# KEY_GPIO_NANDF_ENET.net
KiCad netlist of a schematic drawn in Altium Designer
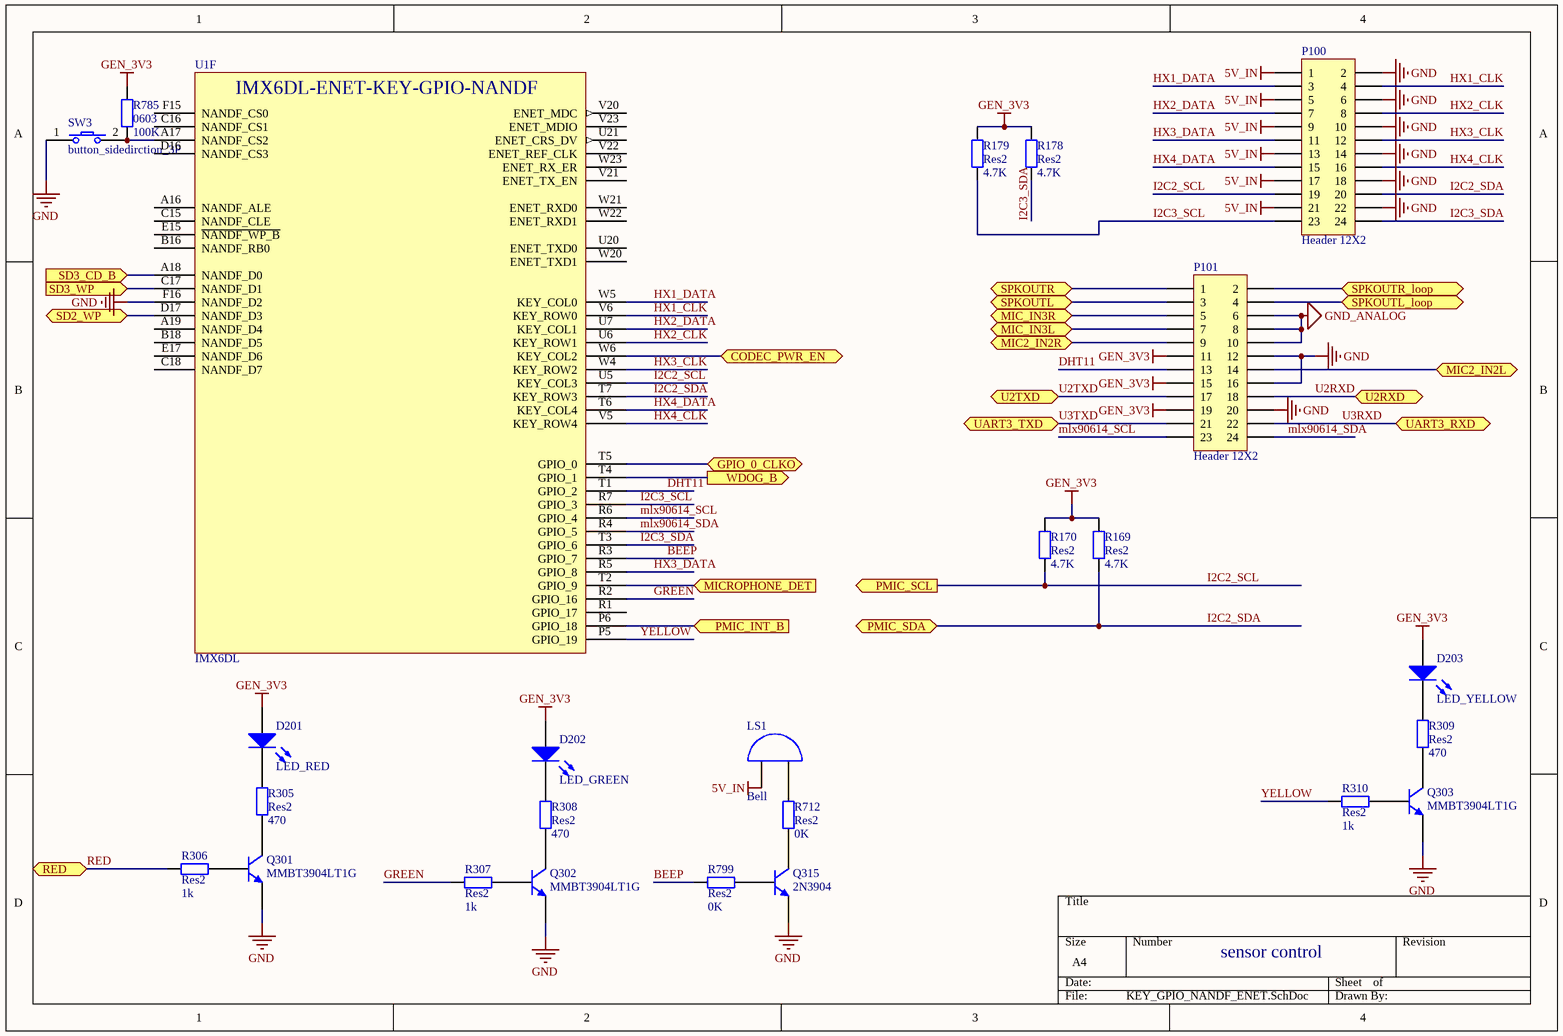
[diagram p0: KEY_GPIO_NANDF_ENET.SchDoc]

(export (version "E")
  (design (tool "Eeschema 10.0.6"))
  (components
    (comp (ref "D201")
      (value "LED_RED")
      (footprint "LED_0603")
      (description "Typical INFRARED GaAs LED")
      (fields (field (name "PUBLISHER") "Altium Limited"))
      (libsource (lib "Miscellaneous Devices") (part "LED0"))
    )
    (comp (ref "D202")
      (value "LED_GREEN")
      (footprint "LED_0603")
      (description "Typical INFRARED GaAs LED")
      (fields (field (name "PUBLISHER") "Altium Limited"))
      (libsource (lib "Miscellaneous Devices") (part "LED0"))
    )
    (comp (ref "D203")
      (value "LED_YELLOW")
      (footprint "LED_0603")
      (description "Typical INFRARED GaAs LED")
      (fields (field (name "PUBLISHER") "Altium Limited"))
      (libsource (lib "Miscellaneous Devices") (part "LED0"))
    )
    (comp (ref "LS1")
      (value "Bell")
      (footprint "PIN2")
      (description "Electrical Bell")
      (fields (field (name "PUBLISHER") "Altium Limited"))
      (libsource (lib "Miscellaneous Devices") (part "Bell"))
    )
    (comp (ref "P100")
      (value "Header 12X2")
      (footprint "Double Row _DIP43025- 2P-24P")
      (description "Header, 12-Pin, Dual row")
      (fields (field (name "PUBLISHER") "Altium Limited"))
      (libsource (lib "Miscellaneous Connectors") (part "Header 12X2"))
    )
    (comp (ref "P101")
      (value "Header 12X2")
      (footprint "Double Row _DIP43025- 2P-24P")
      (description "Header, 12-Pin, Dual row")
      (fields (field (name "PUBLISHER") "Altium Limited"))
      (libsource (lib "Miscellaneous Connectors") (part "Header 12X2"))
    )
    (comp (ref "Q301")
      (value "MMBT3904LT1G")
      (footprint "MMBT3904LT1G-SOT23")
      (libsource (lib "IMX6DL") (part "MMBT3904LT1G"))
    )
    (comp (ref "Q302")
      (value "MMBT3904LT1G")
      (footprint "MMBT3904LT1G-SOT23")
      (libsource (lib "IMX6DL") (part "MMBT3904LT1G"))
    )
    (comp (ref "Q303")
      (value "MMBT3904LT1G")
      (footprint "MMBT3904LT1G-SOT23")
      (libsource (lib "IMX6DL") (part "MMBT3904LT1G"))
    )
    (comp (ref "Q315")
      (value "2N3904")
      (footprint "BCY-W3/E4")
      (description "NPN General Purpose Amplifier")
      (fields (field (name "PUBLISHER") "Altium Limited"))
      (libsource (lib "Miscellaneous Devices") (part "2N3904"))
    )
    (comp (ref "R169")
      (value "Res2")
      (footprint "0402")
      (description "Resistor")
      (fields (field (name "ALTIUM_VALUE") "4.7K") (field (name "PUBLISHER") "Altium Limited"))
      (libsource (lib "") (part "Res2_2"))
    )
    (comp (ref "R170")
      (value "Res2")
      (footprint "0402")
      (description "Resistor")
      (fields (field (name "ALTIUM_VALUE") "4.7K") (field (name "PUBLISHER") "Altium Limited"))
      (libsource (lib "") (part "Res2_2"))
    )
    (comp (ref "R178")
      (value "Res2")
      (footprint "0402")
      (description "Resistor")
      (fields (field (name "ALTIUM_VALUE") "4.7K") (field (name "PUBLISHER") "Altium Limited"))
      (libsource (lib "") (part "Res2_2"))
    )
    (comp (ref "R179")
      (value "Res2")
      (footprint "0402")
      (description "Resistor")
      (fields (field (name "ALTIUM_VALUE") "4.7K") (field (name "PUBLISHER") "Altium Limited"))
      (libsource (lib "") (part "Res2_2"))
    )
    (comp (ref "R305")
      (value "Res2")
      (footprint "0603")
      (description "Resistor")
      (fields (field (name "ALTIUM_VALUE") "470") (field (name "PUBLISHER") "Altium Limited"))
      (libsource (lib "") (part "Res2_2"))
    )
    (comp (ref "R306")
      (value "Res2")
      (footprint "0603")
      (description "Resistor")
      (fields (field (name "ALTIUM_VALUE") "1k") (field (name "PUBLISHER") "Altium Limited"))
      (libsource (lib "Miscellaneous Devices") (part "Res2"))
    )
    (comp (ref "R307")
      (value "Res2")
      (footprint "0603")
      (description "Resistor")
      (fields (field (name "ALTIUM_VALUE") "1k") (field (name "PUBLISHER") "Altium Limited"))
      (libsource (lib "Miscellaneous Devices") (part "Res2"))
    )
    (comp (ref "R308")
      (value "Res2")
      (footprint "0603")
      (description "Resistor")
      (fields (field (name "ALTIUM_VALUE") "470") (field (name "PUBLISHER") "Altium Limited"))
      (libsource (lib "") (part "Res2_2"))
    )
    (comp (ref "R309")
      (value "Res2")
      (footprint "0603")
      (description "Resistor")
      (fields (field (name "ALTIUM_VALUE") "470") (field (name "PUBLISHER") "Altium Limited"))
      (libsource (lib "") (part "Res2_2"))
    )
    (comp (ref "R310")
      (value "Res2")
      (footprint "0603")
      (description "Resistor")
      (fields (field (name "ALTIUM_VALUE") "1k") (field (name "PUBLISHER") "Altium Limited"))
      (libsource (lib "Miscellaneous Devices") (part "Res2"))
    )
    (comp (ref "R712")
      (value "Res2")
      (footprint "0603")
      (description "Resistor")
      (fields (field (name "ALTIUM_VALUE") "0K") (field (name "PUBLISHER") "Altium Limited"))
      (libsource (lib "") (part "Res2_1"))
    )
    (comp (ref "R785")
      (value "0603")
      (footprint "0603")
      (description "Resistor")
      (fields (field (name "ALTIUM_VALUE") "100K") (field (name "PUBLISHER") "Altium Limited"))
      (libsource (lib "") (part "Res2_2"))
    )
    (comp (ref "R799")
      (value "Res2")
      (footprint "0603")
      (description "Resistor")
      (fields (field (name "ALTIUM_VALUE") "0K") (field (name "PUBLISHER") "Altium Limited"))
      (libsource (lib "Miscellaneous Devices") (part "Res2"))
    )
    (comp (ref "SW3")
      (value "button_sidedirction_3P")
      (footprint "button_sidedirction_3P 4.5X4.5")
      (libsource (lib "IMX6DL") (part "button_sidedirction_3P"))
    )
    (comp (ref "U1")
      (value "IMX6DL")
      (footprint "IMX6DL-BGA624x25")
      (libsource (lib "IMX6DL") (part "IMX6DL"))
    )
  )
  (nets
    (net (code "1") (name "/BEEP") (class "Default")
      (node (ref "R799") (pin "2") (pinfunction "2_2") (pintype "passive"))
      (node (ref "U1") (pin "R3") (pinfunction "GPIO_7_R3") (pintype "passive"))
    )
    (net (code "2") (name "/CODEC_PWR_EN") (class "Default")
      (node (ref "U1") (pin "W6") (pinfunction "KEY_COL2_W6") (pintype "passive"))
    )
    (net (code "3") (name "/DHT11") (class "Default")
      (node (ref "P101") (pin "13") (pinfunction "13_13") (pintype "passive"))
      (node (ref "U1") (pin "T1") (pinfunction "GPIO_2_T1") (pintype "passive"))
    )
    (net (code "4") (name "/GPIO_0_CLKO") (class "Default")
      (node (ref "U1") (pin "T5") (pinfunction "GPIO_0_T5") (pintype "passive"))
    )
    (net (code "5") (name "/GREEN") (class "Default")
      (node (ref "R307") (pin "2") (pinfunction "2_2") (pintype "passive"))
      (node (ref "U1") (pin "R2") (pinfunction "GPIO_16_R2") (pintype "passive"))
    )
    (net (code "6") (name "/HX1_CLK") (class "Default")
      (node (ref "P100") (pin "4") (pinfunction "4_4") (pintype "passive"))
      (node (ref "U1") (pin "V6") (pinfunction "KEY_ROW0_V6") (pintype "passive"))
    )
    (net (code "7") (name "/HX1_DATA") (class "Default")
      (node (ref "P100") (pin "3") (pinfunction "3_3") (pintype "passive"))
      (node (ref "U1") (pin "W5") (pinfunction "KEY_COL0_W5") (pintype "passive"))
    )
    (net (code "8") (name "/HX2_CLK") (class "Default")
      (node (ref "P100") (pin "8") (pinfunction "8_8") (pintype "passive"))
      (node (ref "U1") (pin "U6") (pinfunction "KEY_ROW1_U6") (pintype "passive"))
    )
    (net (code "9") (name "/HX2_DATA") (class "Default")
      (node (ref "P100") (pin "7") (pinfunction "7_7") (pintype "passive"))
      (node (ref "U1") (pin "U7") (pinfunction "KEY_COL1_U7") (pintype "passive"))
    )
    (net (code "10") (name "/HX3_CLK") (class "Default")
      (node (ref "P100") (pin "12") (pinfunction "12_12") (pintype "passive"))
      (node (ref "U1") (pin "W4") (pinfunction "KEY_ROW2_W4") (pintype "passive"))
    )
    (net (code "11") (name "/HX3_DATA") (class "Default")
      (node (ref "P100") (pin "11") (pinfunction "11_11") (pintype "passive"))
      (node (ref "U1") (pin "R5") (pinfunction "GPIO_8_R5") (pintype "passive"))
    )
    (net (code "12") (name "/HX4_CLK") (class "Default")
      (node (ref "P100") (pin "16") (pinfunction "16_16") (pintype "passive"))
      (node (ref "U1") (pin "V5") (pinfunction "KEY_ROW4_V5") (pintype "passive"))
    )
    (net (code "13") (name "/HX4_DATA") (class "Default")
      (node (ref "P100") (pin "15") (pinfunction "15_15") (pintype "passive"))
      (node (ref "U1") (pin "T6") (pinfunction "KEY_COL4_T6") (pintype "passive"))
    )
    (net (code "14") (name "/I2C2_SCL") (class "Default")
      (node (ref "P100") (pin "19") (pinfunction "19_19") (pintype "passive"))
      (node (ref "R170") (pin "1") (pinfunction "1_1") (pintype "passive"))
      (node (ref "U1") (pin "U5") (pinfunction "KEY_COL3_U5") (pintype "passive"))
    )
    (net (code "15") (name "/I2C2_SDA") (class "Default")
      (node (ref "P100") (pin "20") (pinfunction "20_20") (pintype "passive"))
      (node (ref "R169") (pin "1") (pinfunction "1_1") (pintype "passive"))
      (node (ref "U1") (pin "T7") (pinfunction "KEY_ROW3_T7") (pintype "passive"))
    )
    (net (code "16") (name "/I2C3_SCL") (class "Default")
      (node (ref "P100") (pin "23") (pinfunction "23_23") (pintype "passive"))
      (node (ref "R179") (pin "1") (pinfunction "1_1") (pintype "passive"))
      (node (ref "U1") (pin "R7") (pinfunction "GPIO_3_R7") (pintype "passive"))
    )
    (net (code "17") (name "/I2C3_SDA") (class "Default")
      (node (ref "P100") (pin "24") (pinfunction "24_24") (pintype "passive"))
      (node (ref "R178") (pin "1") (pinfunction "1_1") (pintype "passive"))
      (node (ref "U1") (pin "T3") (pinfunction "GPIO_6_T3") (pintype "passive"))
    )
    (net (code "18") (name "/MIC2_IN2L") (class "Default")
      (node (ref "P101") (pin "14") (pinfunction "14_14") (pintype "passive"))
    )
    (net (code "19") (name "/MIC2_IN2R") (class "Default")
      (node (ref "P101") (pin "9") (pinfunction "9_9") (pintype "passive"))
    )
    (net (code "20") (name "/MICROPHONE_DET") (class "Default")
      (node (ref "U1") (pin "T2") (pinfunction "GPIO_9_T2") (pintype "passive"))
    )
    (net (code "21") (name "/MIC_IN3L") (class "Default")
      (node (ref "P101") (pin "7") (pinfunction "7_7") (pintype "passive"))
    )
    (net (code "22") (name "/MIC_IN3R") (class "Default")
      (node (ref "P101") (pin "5") (pinfunction "5_5") (pintype "passive"))
    )
    (net (code "23") (name "/PMIC_INT_B") (class "Default")
      (node (ref "U1") (pin "P6") (pinfunction "GPIO_18_P6") (pintype "passive"))
    )
    (net (code "24") (name "/RED") (class "Default")
      (node (ref "R306") (pin "2") (pinfunction "2_2") (pintype "passive"))
    )
    (net (code "25") (name "/SD2_WP") (class "Default")
      (node (ref "U1") (pin "D17") (pinfunction "NANDF_D3_D17") (pintype "passive"))
    )
    (net (code "26") (name "/SD3_CD_B") (class "Default")
      (node (ref "U1") (pin "A18") (pinfunction "NANDF_D0_A18") (pintype "passive"))
    )
    (net (code "27") (name "/SD3_WP") (class "Default")
      (node (ref "U1") (pin "C17") (pinfunction "NANDF_D1_C17") (pintype "passive"))
    )
    (net (code "28") (name "/SPKOUTL") (class "Default")
      (node (ref "P101") (pin "3") (pinfunction "3_3") (pintype "passive"))
    )
    (net (code "29") (name "/SPKOUTL_loop") (class "Default")
      (node (ref "P101") (pin "4") (pinfunction "4_4") (pintype "passive"))
    )
    (net (code "30") (name "/SPKOUTR") (class "Default")
      (node (ref "P101") (pin "1") (pinfunction "1_1") (pintype "passive"))
    )
    (net (code "31") (name "/SPKOUTR_loop") (class "Default")
      (node (ref "P101") (pin "2") (pinfunction "2_2") (pintype "passive"))
    )
    (net (code "32") (name "/U2RXD") (class "Default")
      (node (ref "P101") (pin "18") (pinfunction "18_18") (pintype "passive"))
    )
    (net (code "33") (name "/U2TXD") (class "Default")
      (node (ref "P101") (pin "17") (pinfunction "17_17") (pintype "passive"))
    )
    (net (code "34") (name "/U3RXD") (class "Default")
      (node (ref "P101") (pin "22") (pinfunction "22_22") (pintype "passive"))
    )
    (net (code "35") (name "/U3TXD") (class "Default")
      (node (ref "P101") (pin "21") (pinfunction "21_21") (pintype "passive"))
    )
    (net (code "36") (name "/WDOG_B") (class "Default")
      (node (ref "U1") (pin "T4") (pinfunction "GPIO_1_T4") (pintype "passive"))
    )
    (net (code "37") (name "/YELLOW") (class "Default")
      (node (ref "R310") (pin "2") (pinfunction "2_2") (pintype "passive"))
      (node (ref "U1") (pin "P5") (pinfunction "GPIO_19_P5") (pintype "passive"))
    )
    (net (code "38") (name "/mlx90614_SCL") (class "Default")
      (node (ref "P101") (pin "23") (pinfunction "23_23") (pintype "passive"))
      (node (ref "U1") (pin "R6") (pinfunction "GPIO_4_R6") (pintype "passive"))
    )
    (net (code "39") (name "/mlx90614_SDA") (class "Default")
      (node (ref "P101") (pin "24") (pinfunction "24_24") (pintype "passive"))
      (node (ref "U1") (pin "R4") (pinfunction "GPIO_5_R4") (pintype "passive"))
    )
    (net (code "40") (name "5V_IN") (class "Default")
      (node (ref "LS1") (pin "1") (pinfunction "A_1") (pintype "passive"))
      (node (ref "P100") (pin "1") (pinfunction "1_1") (pintype "passive"))
      (node (ref "P100") (pin "13") (pinfunction "13_13") (pintype "passive"))
      (node (ref "P100") (pin "17") (pinfunction "17_17") (pintype "passive"))
      (node (ref "P100") (pin "21") (pinfunction "21_21") (pintype "passive"))
      (node (ref "P100") (pin "5") (pinfunction "5_5") (pintype "passive"))
      (node (ref "P100") (pin "9") (pinfunction "9_9") (pintype "passive"))
    )
    (net (code "41") (name "GEN_3V3") (class "Default")
      (node (ref "D201") (pin "1") (pinfunction "A_1") (pintype "passive"))
      (node (ref "D202") (pin "1") (pinfunction "A_1") (pintype "passive"))
      (node (ref "D203") (pin "1") (pinfunction "A_1") (pintype "passive"))
      (node (ref "P101") (pin "11") (pinfunction "11_11") (pintype "passive"))
      (node (ref "P101") (pin "15") (pinfunction "15_15") (pintype "passive"))
      (node (ref "P101") (pin "19") (pinfunction "19_19") (pintype "passive"))
      (node (ref "R169") (pin "2") (pinfunction "2_2") (pintype "passive"))
      (node (ref "R170") (pin "2") (pinfunction "2_2") (pintype "passive"))
      (node (ref "R178") (pin "2") (pinfunction "2_2") (pintype "passive"))
      (node (ref "R179") (pin "2") (pinfunction "2_2") (pintype "passive"))
      (node (ref "R785") (pin "2") (pinfunction "2_2") (pintype "passive"))
    )
    (net (code "42") (name "GND") (class "Default")
      (node (ref "P100") (pin "10") (pinfunction "10_10") (pintype "passive"))
      (node (ref "P100") (pin "14") (pinfunction "14_14") (pintype "passive"))
      (node (ref "P100") (pin "18") (pinfunction "18_18") (pintype "passive"))
      (node (ref "P100") (pin "2") (pinfunction "2_2") (pintype "passive"))
      (node (ref "P100") (pin "22") (pinfunction "22_22") (pintype "passive"))
      (node (ref "P100") (pin "6") (pinfunction "6_6") (pintype "passive"))
      (node (ref "P101") (pin "12") (pinfunction "12_12") (pintype "passive"))
      (node (ref "P101") (pin "16") (pinfunction "16_16") (pintype "passive"))
      (node (ref "P101") (pin "20") (pinfunction "20_20") (pintype "passive"))
      (node (ref "Q301") (pin "2") (pinfunction "E_2") (pintype "passive"))
      (node (ref "Q302") (pin "2") (pinfunction "E_2") (pintype "passive"))
      (node (ref "Q303") (pin "2") (pinfunction "E_2") (pintype "passive"))
      (node (ref "Q315") (pin "1") (pinfunction "E_1") (pintype "passive"))
      (node (ref "SW3") (pin "1") (pinfunction "3_1") (pintype "passive"))
      (node (ref "U1") (pin "F16") (pinfunction "NANDF_D2_F16") (pintype "passive"))
    )
    (net (code "43") (name "GND_ANALOG") (class "Default")
      (node (ref "P101") (pin "10") (pinfunction "10_10") (pintype "passive"))
      (node (ref "P101") (pin "6") (pinfunction "6_6") (pintype "passive"))
      (node (ref "P101") (pin "8") (pinfunction "8_8") (pintype "passive"))
    )
    (net (code "44") (name "Net-(D201-K)") (class "Default")
      (node (ref "D201") (pin "2") (pinfunction "K_2") (pintype "passive"))
      (node (ref "R305") (pin "2") (pinfunction "2_2") (pintype "passive"))
    )
    (net (code "45") (name "Net-(D202-K)") (class "Default")
      (node (ref "D202") (pin "2") (pinfunction "K_2") (pintype "passive"))
      (node (ref "R308") (pin "2") (pinfunction "2_2") (pintype "passive"))
    )
    (net (code "46") (name "Net-(D203-K)") (class "Default")
      (node (ref "D203") (pin "2") (pinfunction "K_2") (pintype "passive"))
      (node (ref "R309") (pin "2") (pinfunction "2_2") (pintype "passive"))
    )
    (net (code "47") (name "Net-(LS1-B)") (class "Default")
      (node (ref "LS1") (pin "2") (pinfunction "B_2") (pintype "passive"))
      (node (ref "R712") (pin "1") (pinfunction "1_1") (pintype "passive"))
    )
    (net (code "48") (name "Net-(Q301-B)") (class "Default")
      (node (ref "Q301") (pin "1") (pinfunction "B_1") (pintype "passive"))
      (node (ref "R306") (pin "1") (pinfunction "1_1") (pintype "passive"))
    )
    (net (code "49") (name "Net-(Q301-Pad3)") (class "Default")
      (node (ref "Q301") (pin "3") (pinfunction "3_3") (pintype "passive"))
      (node (ref "R305") (pin "1") (pinfunction "1_1") (pintype "passive"))
    )
    (net (code "50") (name "Net-(Q302-B)") (class "Default")
      (node (ref "Q302") (pin "1") (pinfunction "B_1") (pintype "passive"))
      (node (ref "R307") (pin "1") (pinfunction "1_1") (pintype "passive"))
    )
    (net (code "51") (name "Net-(Q302-Pad3)") (class "Default")
      (node (ref "Q302") (pin "3") (pinfunction "3_3") (pintype "passive"))
      (node (ref "R308") (pin "1") (pinfunction "1_1") (pintype "passive"))
    )
    (net (code "52") (name "Net-(Q303-B)") (class "Default")
      (node (ref "Q303") (pin "1") (pinfunction "B_1") (pintype "passive"))
      (node (ref "R310") (pin "1") (pinfunction "1_1") (pintype "passive"))
    )
    (net (code "53") (name "Net-(Q303-Pad3)") (class "Default")
      (node (ref "Q303") (pin "3") (pinfunction "3_3") (pintype "passive"))
      (node (ref "R309") (pin "1") (pinfunction "1_1") (pintype "passive"))
    )
    (net (code "54") (name "Net-(Q315-B)") (class "Default")
      (node (ref "Q315") (pin "2") (pinfunction "B_2") (pintype "passive"))
      (node (ref "R799") (pin "1") (pinfunction "1_1") (pintype "passive"))
    )
    (net (code "55") (name "Net-(Q315-C)") (class "Default")
      (node (ref "Q315") (pin "3") (pinfunction "C_3") (pintype "passive"))
      (node (ref "R712") (pin "2") (pinfunction "2_2") (pintype "passive"))
    )
    (net (code "56") (name "Net-(U1F-NANDF_CS2)") (class "Default")
      (node (ref "R785") (pin "1") (pinfunction "1_1") (pintype "passive"))
      (node (ref "SW3") (pin "2") (pinfunction "2_2") (pintype "passive"))
      (node (ref "U1") (pin "A17") (pinfunction "NANDF_CS2_A17") (pintype "passive"))
    )
    (net (code "57") (name "unconnected-(U1F-ENET_CRS_DV-PadU21)") (class "Default")
      (node (ref "U1") (pin "U21") (pinfunction "ENET_CRS_DV_U21") (pintype "output"))
    )
    (net (code "58") (name "unconnected-(U1F-ENET_MDC-PadV20)") (class "Default")
      (node (ref "U1") (pin "V20") (pinfunction "ENET_MDC_V20") (pintype "output"))
    )
    (net (code "59") (name "unconnected-(U1F-ENET_MDIO-PadV23)") (class "Default")
      (node (ref "U1") (pin "V23") (pinfunction "ENET_MDIO_V23") (pintype "passive"))
    )
    (net (code "60") (name "unconnected-(U1F-ENET_REF_CLK-PadV22)") (class "Default")
      (node (ref "U1") (pin "V22") (pinfunction "ENET_REF_CLK_V22") (pintype "passive"))
    )
    (net (code "61") (name "unconnected-(U1F-ENET_RXD0-PadW21)") (class "Default")
      (node (ref "U1") (pin "W21") (pinfunction "ENET_RXD0_W21") (pintype "passive"))
    )
    (net (code "62") (name "unconnected-(U1F-ENET_RXD1-PadW22)") (class "Default")
      (node (ref "U1") (pin "W22") (pinfunction "ENET_RXD1_W22") (pintype "passive"))
    )
    (net (code "63") (name "unconnected-(U1F-ENET_RX_ER-PadW23)") (class "Default")
      (node (ref "U1") (pin "W23") (pinfunction "ENET_RX_ER_W23") (pintype "passive"))
    )
    (net (code "64") (name "unconnected-(U1F-ENET_TXD0-PadU20)") (class "Default")
      (node (ref "U1") (pin "U20") (pinfunction "ENET_TXD0_U20") (pintype "passive"))
    )
    (net (code "65") (name "unconnected-(U1F-ENET_TXD1-PadW20)") (class "Default")
      (node (ref "U1") (pin "W20") (pinfunction "ENET_TXD1_W20") (pintype "passive"))
    )
    (net (code "66") (name "unconnected-(U1F-ENET_TX_EN-PadV21)") (class "Default")
      (node (ref "U1") (pin "V21") (pinfunction "ENET_TX_EN_V21") (pintype "passive"))
    )
    (net (code "67") (name "unconnected-(U1F-GPIO_17-PadR1)") (class "Default")
      (node (ref "U1") (pin "R1") (pinfunction "GPIO_17_R1") (pintype "passive"))
    )
    (net (code "68") (name "unconnected-(U1F-NANDF_ALE-PadA16)") (class "Default")
      (node (ref "U1") (pin "A16") (pinfunction "NANDF_ALE_A16") (pintype "passive"))
    )
    (net (code "69") (name "unconnected-(U1F-NANDF_CLE-PadC15)") (class "Default")
      (node (ref "U1") (pin "C15") (pinfunction "NANDF_CLE_C15") (pintype "passive"))
    )
    (net (code "70") (name "unconnected-(U1F-NANDF_CS0-PadF15)") (class "Default")
      (node (ref "U1") (pin "F15") (pinfunction "NANDF_CS0_F15") (pintype "passive"))
    )
    (net (code "71") (name "unconnected-(U1F-NANDF_CS1-PadC16)") (class "Default")
      (node (ref "U1") (pin "C16") (pinfunction "NANDF_CS1_C16") (pintype "passive"))
    )
    (net (code "72") (name "unconnected-(U1F-NANDF_CS3-PadD16)") (class "Default")
      (node (ref "U1") (pin "D16") (pinfunction "NANDF_CS3_D16") (pintype "passive"))
    )
    (net (code "73") (name "unconnected-(U1F-NANDF_D4-PadA19)") (class "Default")
      (node (ref "U1") (pin "A19") (pinfunction "NANDF_D4_A19") (pintype "passive"))
    )
    (net (code "74") (name "unconnected-(U1F-NANDF_D5-PadB18)") (class "Default")
      (node (ref "U1") (pin "B18") (pinfunction "NANDF_D5_B18") (pintype "passive"))
    )
    (net (code "75") (name "unconnected-(U1F-NANDF_D6-PadE17)") (class "Default")
      (node (ref "U1") (pin "E17") (pinfunction "NANDF_D6_E17") (pintype "passive"))
    )
    (net (code "76") (name "unconnected-(U1F-NANDF_D7-PadC18)") (class "Default")
      (node (ref "U1") (pin "C18") (pinfunction "NANDF_D7_C18") (pintype "passive"))
    )
    (net (code "77") (name "unconnected-(U1F-NANDF_RB0-PadB16)") (class "Default")
      (node (ref "U1") (pin "B16") (pinfunction "NANDF_RB0_B16") (pintype "passive"))
    )
    (net (code "78") (name "unconnected-(U1F-~{NANDF_WP_B}-PadE15)") (class "Default")
      (node (ref "U1") (pin "E15") (pinfunction "~{NANDF_WP_B}_E15") (pintype "passive"))
    )
  )
)
